# WL-CONNECT.net
KiCad netlist of a schematic drawn in Altium Designer
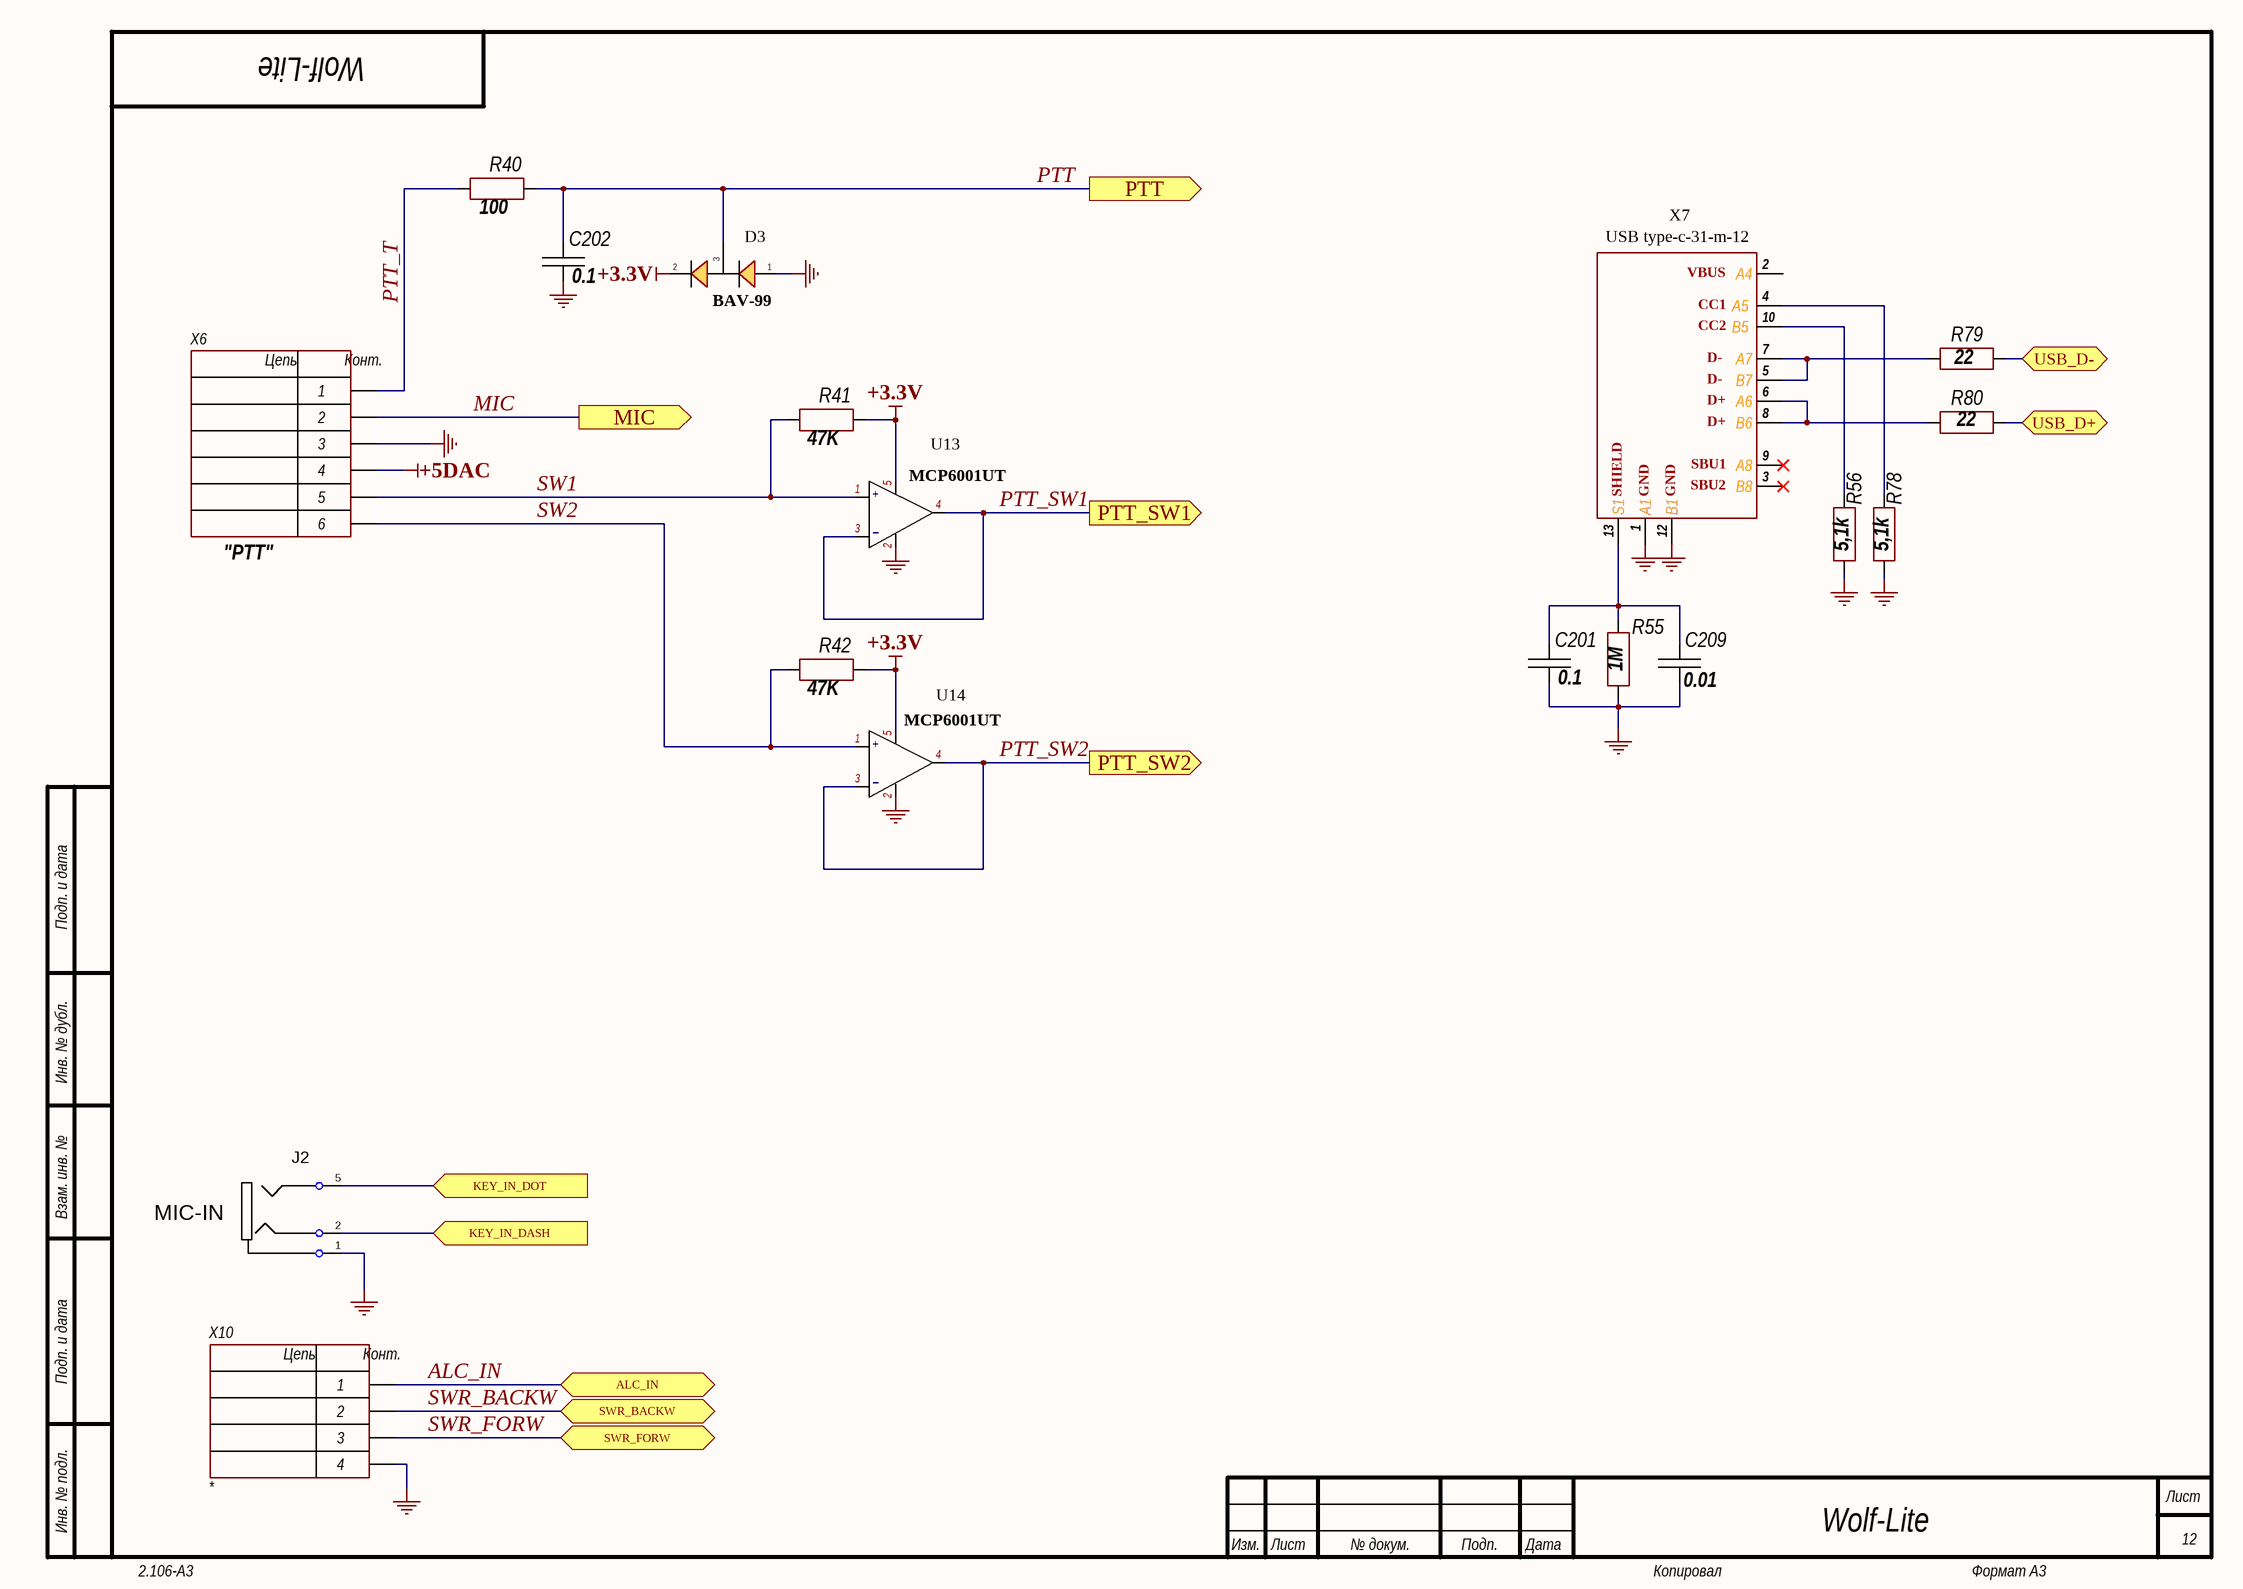
[diagram p0: WL-CONNECT.SchDoc]

(export (version "E")
  (design (tool "Eeschema 10.0.6"))
  (components
    (comp (ref "C201")
      (value "0.1")
      (footprint "standard:CH0805C")
      (libsource (lib "Discrete") (part "Capacitor"))
    )
    (comp (ref "C202")
      (value "0.1")
      (footprint "standard:CH0805C")
      (libsource (lib "Discrete") (part "Capacitor"))
    )
    (comp (ref "C209")
      (value "0.01")
      (footprint "standard:CH0805C")
      (libsource (lib "Discrete") (part "Capacitor"))
    )
    (comp (ref "D3")
      (value "BAV-99")
      (footprint "standard:SOT23_132")
      (libsource (lib "Analog") (part "BAV-99"))
    )
    (comp (ref "J2")
      (value "MIC-IN")
      (footprint "3.5-stereo")
      (description "SJ1-3525NG")
      (libsource (lib "*") (part "SJ1-3523N"))
    )
    (comp (ref "R40") (value "100") (footprint "standard:CH0805R") (libsource (lib "") (part "Resistor_1")))
    (comp (ref "R41") (value "47K") (footprint "standard:CH0805R") (libsource (lib "") (part "Resistor_1")))
    (comp (ref "R42") (value "47K") (footprint "standard:CH0805R") (libsource (lib "") (part "Resistor_1")))
    (comp (ref "R55")
      (value "1M")
      (footprint "standard:CH0805R")
      (libsource (lib "Discrete") (part "Resistor"))
    )
    (comp (ref "R56")
      (value "5,1k")
      (footprint "standard:CH0805R")
      (libsource (lib "Discrete") (part "Resistor"))
    )
    (comp (ref "R78")
      (value "5,1k")
      (footprint "standard:CH0805R")
      (libsource (lib "Discrete") (part "Resistor"))
    )
    (comp (ref "R79") (value "22") (footprint "standard:CH0805R") (libsource (lib "") (part "Resistor_1")))
    (comp (ref "R80") (value "22") (footprint "standard:CH0805R") (libsource (lib "") (part "Resistor_1")))
    (comp (ref "U13")
      (value "MCP6001UT")
      (footprint "SOT23-5")
      (libsource (lib "Analog") (part "MCP6001UT_1"))
    )
    (comp (ref "U14")
      (value "MCP6001UT")
      (footprint "SOT23-5")
      (libsource (lib "Analog") (part "MCP6001UT_1"))
    )
    (comp (ref "X6")
      (value "\"PTT\"")
      (footprint "RJ25-6pin")
      (libsource (lib "Connectors") (part "6-Connector"))
    )
    (comp (ref "X7")
      (value "USB type-c-31-m-12")
      (footprint "TYPE-C-31-M-12_V1")
      (libsource (lib "Connectors") (part "USB-C_2.0"))
    )
    (comp (ref "X10")
      (value "*")
      (footprint "custom:CON: PLS-4")
      (libsource (lib "Connectors") (part "4-Connector"))
    )
  )
  (nets
    (net (code "1") (name "+3.3V") (class "Default")
      (node (ref "D3") (pin "2") (pinfunction "1_2") (pintype "passive"))
      (node (ref "R41") (pin "2") (pinfunction "2_2") (pintype "passive"))
      (node (ref "R42") (pin "2") (pinfunction "2_2") (pintype "passive"))
      (node (ref "U13") (pin "5") (pinfunction "5_5") (pintype "passive"))
      (node (ref "U14") (pin "5") (pinfunction "5_5") (pintype "passive"))
    )
    (net (code "2") (name "+5DAC") (class "Default")
      (node (ref "X6") (pin "4") (pinfunction "4_4") (pintype "power_in"))
    )
    (net (code "3") (name "/ALC_IN") (class "Default")
      (node (ref "X10") (pin "1") (pinfunction "1_1") (pintype "passive"))
    )
    (net (code "4") (name "/KEY_IN_DASH") (class "Default")
      (node (ref "J2") (pin "2") (pinfunction "5_2") (pintype "passive"))
    )
    (net (code "5") (name "/KEY_IN_DOT") (class "Default")
      (node (ref "J2") (pin "5") (pinfunction "2_5") (pintype "passive"))
    )
    (net (code "6") (name "/MIC") (class "Default")
      (node (ref "X6") (pin "2") (pinfunction "2_2") (pintype "passive"))
    )
    (net (code "7") (name "/PTT") (class "Default")
      (node (ref "C202") (pin "2") (pinfunction "2_2") (pintype "power_in"))
      (node (ref "D3") (pin "3") (pinfunction "3_3") (pintype "passive"))
      (node (ref "R40") (pin "2") (pinfunction "2_2") (pintype "passive"))
    )
    (net (code "8") (name "/PTT_SW1") (class "Default")
      (node (ref "U13") (pin "3") (pinfunction "3_3") (pintype "passive"))
      (node (ref "U13") (pin "4") (pinfunction "4_4") (pintype "passive"))
    )
    (net (code "9") (name "/PTT_SW2") (class "Default")
      (node (ref "U14") (pin "3") (pinfunction "3_3") (pintype "passive"))
      (node (ref "U14") (pin "4") (pinfunction "4_4") (pintype "passive"))
    )
    (net (code "10") (name "/PTT_T") (class "Default")
      (node (ref "R40") (pin "1") (pinfunction "1_1") (pintype "passive"))
      (node (ref "X6") (pin "1") (pinfunction "1_1") (pintype "passive"))
    )
    (net (code "11") (name "/SW1") (class "Default")
      (node (ref "R41") (pin "1") (pinfunction "1_1") (pintype "passive"))
      (node (ref "U13") (pin "1") (pinfunction "1_1") (pintype "passive"))
      (node (ref "X6") (pin "5") (pinfunction "5_5") (pintype "power_in"))
    )
    (net (code "12") (name "/SW2") (class "Default")
      (node (ref "R42") (pin "1") (pinfunction "1_1") (pintype "passive"))
      (node (ref "U14") (pin "1") (pinfunction "1_1") (pintype "passive"))
      (node (ref "X6") (pin "6") (pinfunction "6_6") (pintype "power_in"))
    )
    (net (code "13") (name "/SWR_BACKW") (class "Default")
      (node (ref "X10") (pin "2") (pinfunction "2_2") (pintype "passive"))
    )
    (net (code "14") (name "/SWR_FORW") (class "Default")
      (node (ref "X10") (pin "3") (pinfunction "3_3") (pintype "power_in"))
    )
    (net (code "15") (name "/USB_D+") (class "Default")
      (node (ref "R80") (pin "2") (pinfunction "2_2") (pintype "passive"))
    )
    (net (code "16") (name "/USB_D-") (class "Default")
      (node (ref "R79") (pin "2") (pinfunction "2_2") (pintype "passive"))
    )
    (net (code "17") (name "GND") (class "Default")
      (node (ref "C201") (pin "1") (pinfunction "1_1") (pintype "power_in"))
      (node (ref "C202") (pin "1") (pinfunction "1_1") (pintype "power_in"))
      (node (ref "C209") (pin "1") (pinfunction "1_1") (pintype "power_in"))
      (node (ref "D3") (pin "1") (pinfunction "1_1") (pintype "passive"))
      (node (ref "J2") (pin "1") (pinfunction "1_1") (pintype "passive"))
      (node (ref "R55") (pin "1") (pinfunction "1_1") (pintype "passive"))
      (node (ref "R56") (pin "1") (pinfunction "1_1") (pintype "passive"))
      (node (ref "R78") (pin "1") (pinfunction "1_1") (pintype "passive"))
      (node (ref "U13") (pin "2") (pinfunction "2_2") (pintype "passive"))
      (node (ref "U14") (pin "2") (pinfunction "2_2") (pintype "passive"))
      (node (ref "X10") (pin "4") (pinfunction "4_4") (pintype "power_in"))
      (node (ref "X6") (pin "3") (pinfunction "3_3") (pintype "power_in"))
      (node (ref "X7") (pin "1") (pinfunction "A1_1") (pintype "power_in"))
      (node (ref "X7") (pin "12") (pinfunction "B1_12") (pintype "power_in"))
    )
    (net (code "18") (name "Net-(X7-A5)") (class "Default")
      (node (ref "R78") (pin "2") (pinfunction "2_2") (pintype "passive"))
      (node (ref "X7") (pin "4") (pinfunction "A5_4") (pintype "power_in"))
    )
    (net (code "19") (name "Net-(X7-A6)") (class "Default")
      (node (ref "R80") (pin "1") (pinfunction "1_1") (pintype "passive"))
      (node (ref "X7") (pin "6") (pinfunction "A6_6") (pintype "power_in"))
      (node (ref "X7") (pin "8") (pinfunction "B6_8") (pintype "power_in"))
    )
    (net (code "20") (name "Net-(X7-A7)") (class "Default")
      (node (ref "R79") (pin "1") (pinfunction "1_1") (pintype "passive"))
      (node (ref "X7") (pin "5") (pinfunction "B7_5") (pintype "power_in"))
      (node (ref "X7") (pin "7") (pinfunction "A7_7") (pintype "power_in"))
    )
    (net (code "21") (name "Net-(X7-B5)") (class "Default")
      (node (ref "R56") (pin "2") (pinfunction "2_2") (pintype "passive"))
      (node (ref "X7") (pin "10") (pinfunction "B5_10") (pintype "power_in"))
    )
    (net (code "22") (name "Net-(X7-S1)") (class "Default")
      (node (ref "C201") (pin "2") (pinfunction "2_2") (pintype "power_in"))
      (node (ref "C209") (pin "2") (pinfunction "2_2") (pintype "power_in"))
      (node (ref "R55") (pin "2") (pinfunction "2_2") (pintype "passive"))
      (node (ref "X7") (pin "13") (pinfunction "S1_13") (pintype "power_in"))
    )
    (net (code "23") (name "unconnected-(X7-A4-Pad2)") (class "Default")
      (node (ref "X7") (pin "2") (pinfunction "A4_2") (pintype "power_in"))
    )
    (net (code "24") (name "unconnected-(X7-A8-Pad9)") (class "Default")
      (node (ref "X7") (pin "9") (pinfunction "A8_9") (pintype "power_in+no_connect"))
    )
    (net (code "25") (name "unconnected-(X7-B8-Pad3)") (class "Default")
      (node (ref "X7") (pin "3") (pinfunction "B8_3") (pintype "power_in+no_connect"))
    )
  )
)
